# USBC_A.net
KiCad netlist of a schematic drawn in Altium Designer
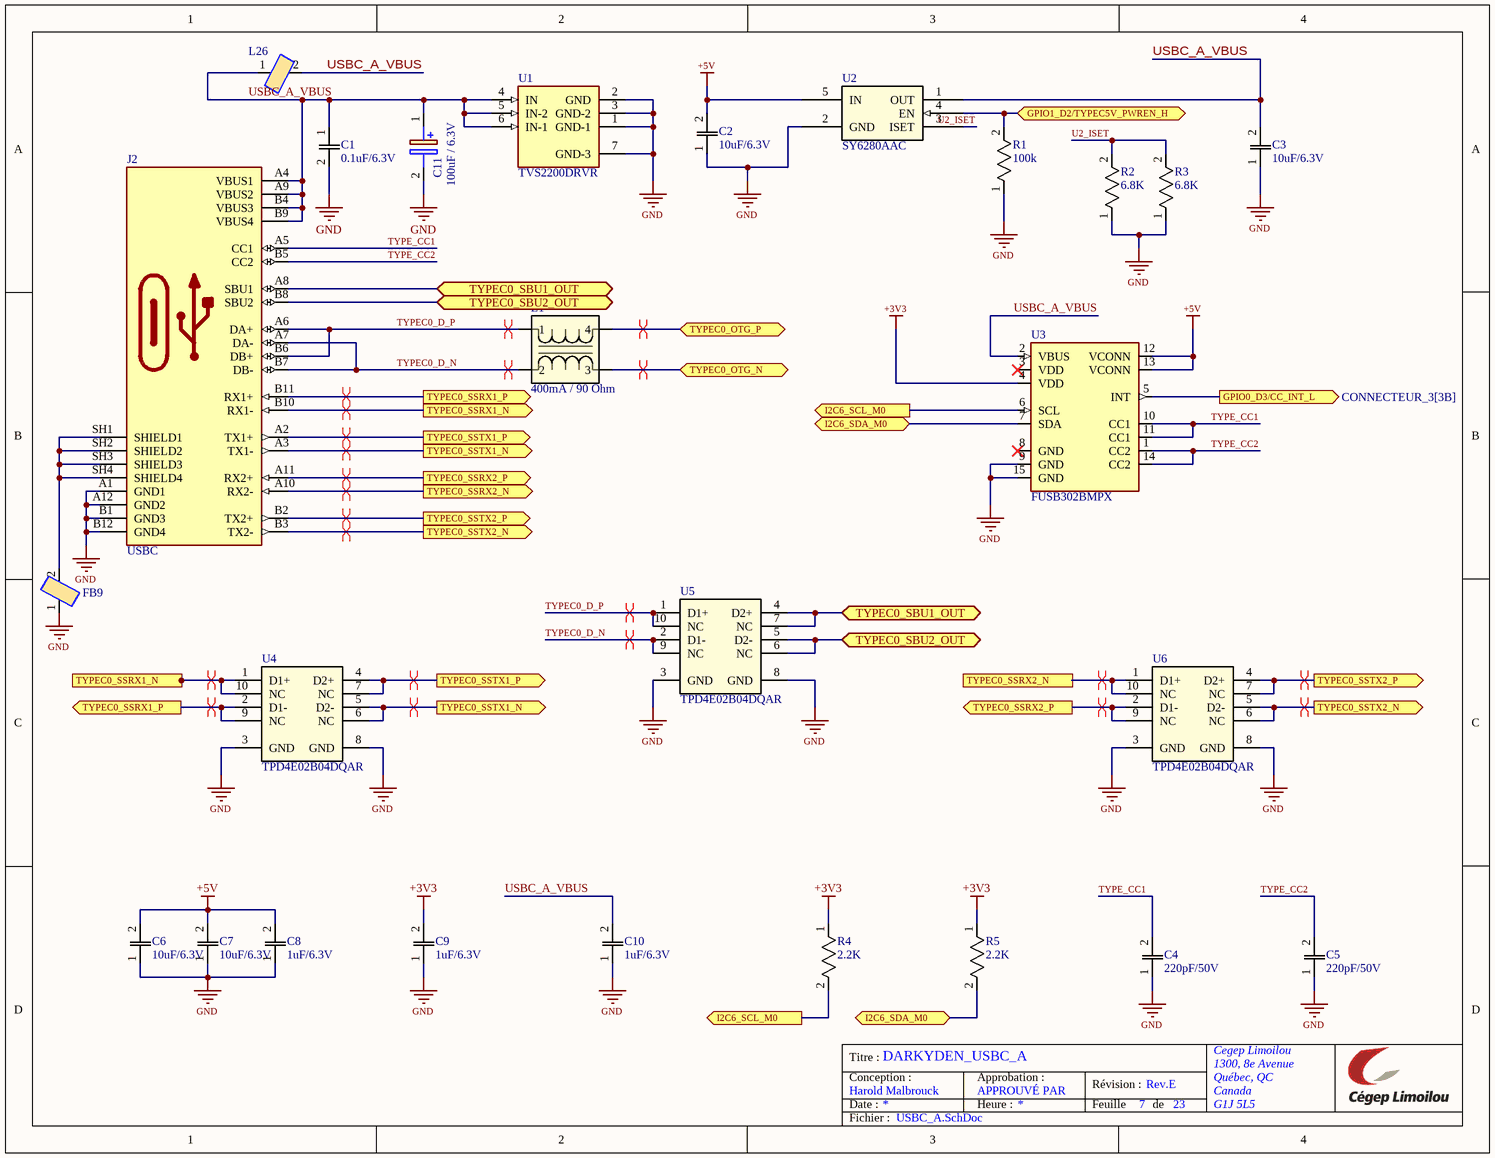
[diagram p0: USBC_A.SchDoc]

(export (version "E")
  (design (tool "Eeschema 10.0.6"))
  (components
    (comp (ref "C1")
      (value "0.1uF/6.3V")
      (footprint "C0805")
      (description "0.1uF 6.3V X7R 10% Pad SMD 0805 125C T/R")
      (fields
        (field (name "MANUFACTURER_PART_NUMBER") "C0805C104K9RACTU")
        (field (name "MOUSER PART NUMBER") "80-C0805C104K9R")
      )
      (libsource (lib "DARKYDEN") (part "C0805C104K9RACTU"))
    )
    (comp (ref "C2")
      (value "10uF/6.3V")
      (footprint "C0805")
      (fields
        (field (name "MANUFACTURER_PART_NUMBER") "C0805C106K9RACTU")
        (field (name "MOUSER PART NUMBER") "80-C0805C106K9R")
        (field (name "MANUFACTURER") "KEMET")
      )
      (libsource (lib "DARKYDEN") (part "C0805C106K9RACTU"))
    )
    (comp (ref "C3")
      (value "10uF/6.3V")
      (footprint "C0805")
      (fields
        (field (name "MANUFACTURER_PART_NUMBER") "C0805C106K9RACTU")
        (field (name "MOUSER PART NUMBER") "80-C0805C106K9R")
        (field (name "MANUFACTURER") "KEMET")
      )
      (libsource (lib "DARKYDEN") (part "C0805C106K9RACTU"))
    )
    (comp (ref "C4")
      (value "220pF/50V")
      (footprint "C0805")
      (description "Cap Ceramic 220pF 50V X7R 20% Pad SMD 0805 125C T/R")
      (fields
        (field (name "MANUFACTURER") "KEMET")
        (field (name "MANUFACTURER PART NUMBER") "C0805C221M5RACTU")
      )
      (libsource (lib "DARKYDEN") (part "C0805C221M5RACTU"))
    )
    (comp (ref "C5")
      (value "220pF/50V")
      (footprint "C0805")
      (description "Cap Ceramic 220pF 50V X7R 20% Pad SMD 0805 125C T/R")
      (fields
        (field (name "MANUFACTURER") "KEMET")
        (field (name "MANUFACTURER PART NUMBER") "C0805C221M5RACTU")
      )
      (libsource (lib "DARKYDEN") (part "C0805C221M5RACTU"))
    )
    (comp (ref "C6")
      (value "10uF/6.3V")
      (footprint "C0805")
      (fields
        (field (name "MANUFACTURER_PART_NUMBER") "C0805C106K9RACTU")
        (field (name "MOUSER PART NUMBER") "80-C0805C106K9R")
        (field (name "MANUFACTURER") "KEMET")
      )
      (libsource (lib "DARKYDEN") (part "C0805C106K9RACTU"))
    )
    (comp (ref "C7")
      (value "10uF/6.3V")
      (footprint "C0805")
      (fields
        (field (name "MANUFACTURER_PART_NUMBER") "C0805C106K9RACTU")
        (field (name "MOUSER PART NUMBER") "80-C0805C106K9R")
        (field (name "MANUFACTURER") "KEMET")
      )
      (libsource (lib "DARKYDEN") (part "C0805C106K9RACTU"))
    )
    (comp (ref "C8")
      (value "1uF/6.3V")
      (footprint "C0805")
      (description "1 uF, 6.3 V, ± 10%, X7R, 0805 [2012 Metric] Multilayer Ceramic Capacitor,")
      (fields
        (field (name "MANUFACTURER_PART_NUMBER") "C0805C105K9RACTU")
        (field (name "MOUSER PART NUMBER") "80-C0805C105K9R")
      )
      (libsource (lib "DARKYDEN") (part "C0805C105K9RACTU"))
    )
    (comp (ref "C9")
      (value "1uF/6.3V")
      (footprint "C0805")
      (description "1 uF, 6.3 V, ± 10%, X7R, 0805 [2012 Metric] Multilayer Ceramic Capacitor,")
      (fields
        (field (name "MANUFACTURER_PART_NUMBER") "C0805C105K9RACTU")
        (field (name "MOUSER PART NUMBER") "80-C0805C105K9R")
      )
      (libsource (lib "DARKYDEN") (part "C0805C105K9RACTU"))
    )
    (comp (ref "C10")
      (value "1uF/6.3V")
      (footprint "C0805")
      (description "1 uF, 6.3 V, ± 10%, X7R, 0805 [2012 Metric] Multilayer Ceramic Capacitor,")
      (fields
        (field (name "MANUFACTURER_PART_NUMBER") "C0805C105K9RACTU")
        (field (name "MOUSER PART NUMBER") "80-C0805C105K9R")
      )
      (libsource (lib "DARKYDEN") (part "C0805C105K9RACTU"))
    )
    (comp (ref "C11")
      (value "100uF / 6.3V")
      (footprint "SamacSys:EEE0GA101SR")
      (description "100uF 6.3V 20% Cap Aluminum Lytic  SMD 0.36 Ohm 240mA 2000h 105C Automotive T/R")
      (fields
        (field (name "MANUFACTURER_PART_NUMBER") "EEE-FPJ101UAR")
        (field (name "MOUSER PART NUMBER") "667-EEE-FPJ101UAR")
      )
      (libsource (lib "SamacSys") (part "EEE-FPJ101UAR"))
    )
    (comp (ref "FB9")
      (value "220R / 100MHz")
      (footprint "SamacSys:BLM18SP221SN1B")
      (description "Ferrite Beads Multi-Layer 220Ohm 25% 100MHz 2A 50mOhm DCR 0603 Paper T/R")
      (fields
        (field (name "MANUFACTURER_PART_NUMBER") "BLM18EG221SN1D")
        (field (name "MOUSER PART NUMBER") "81-BLM18EG221SN1D")
      )
      (libsource (lib "SamacSys") (part "BLM18EG221SN1D"))
    )
    (comp (ref "J2")
      (value "USBC")
      (footprint "USB_C")
      (fields (field (name "MF") "Molex") (field (name "MP") "2012670005"))
      (libsource (lib "DARKYDEN") (part "USBC"))
    )
    (comp (ref "L1")
      (value "400mA / 90 Ohm")
      (footprint "SamacSys:ACM20129002PT002")
      (description "Ferrite Beads Wirewound Common Mode Filter 90Ohm 100MHz 400mA 0805 T/R")
      (fields
        (field (name "MANUFACTURER_PART_NUMBER") "ACM2012-900-2P-T002")
        (field (name "MOUSER PART NUMBER") "810-ACM20129002PT002")
      )
      (libsource (lib "SamacSys") (part "ACM2012-900-2P-T002"))
    )
    (comp (ref "L26")
      (value "FBMJ2125HM210NT")
      (footprint "INDC2012X105N")
      (description "Ferrite Beads Power Chip 21Ohm 30% 100MHz 6A 0.004Ohm DCR 0805 Automotive T/R")
      (fields
        (field (name "MANUFACTURER") "Taiyo Yuden")
        (field (name "MOUSER PART NUMBER") "963-FBMJ2125HM210NT")
      )
      (libsource (lib "SamacSys") (part "FBMJ2125HM210NT"))
    )
    (comp (ref "R1")
      (value "100k")
      (footprint "SamacSys:RESC1608X55N")
      (description "100K Ohm 5%  Res Thick Film 0603 1/10W +/-200ppm/ßC Molded SMD Punched Carrier T/R")
      (fields
        (field (name "MANUFACTURER_PART_NUMBER") "ERJ-3GEYJ104V")
        (field (name "MOUSER PART NUMBER") "667-ERJ-3GEYJ104V")
      )
      (libsource (lib "DARKYDEN") (part "ERJ-3GEYJ104V"))
    )
    (comp (ref "R2")
      (value "6.8K")
      (footprint "SamacSys:RESC1608X55N")
      (description "6.8 kOhm, ± 5%, 100 mW, 0603 [1608 Metric], Thick Film, General Purpose")
      (fields
        (field (name "MANUFACTURER_PART_NUMBER") "ERJ-3GEYJ682V")
        (field (name "MANUFACTURER") "Panasonic")
      )
      (libsource (lib "DARKYDEN") (part "ERJ-3GEYJ682V"))
    )
    (comp (ref "R3")
      (value "6.8K")
      (footprint "SamacSys:RESC1608X55N")
      (description "6.8 kOhm, ± 5%, 100 mW, 0603 [1608 Metric], Thick Film, General Purpose")
      (fields
        (field (name "MANUFACTURER_PART_NUMBER") "ERJ-3GEYJ682V")
        (field (name "MANUFACTURER") "Panasonic")
      )
      (libsource (lib "DARKYDEN") (part "ERJ-3GEYJ682V"))
    )
    (comp (ref "R4")
      (value "2.2K")
      (footprint "SamacSys:RESC1608X55N")
      (description "2.2 kOhm, ï¿½ 5%, 100 mW, 0603 [1608 Metric], Thick Film, General Purpose")
      (fields
        (field (name "MANUFACTURER_PART_NUMBER") "ERJ-3GEYJ222V")
        (field (name "MOUSER PART NUMBER") "667-ERJ-3GEYJ222V")
      )
      (libsource (lib "DARKYDEN") (part "ERJ-3GEYJ222V"))
    )
    (comp (ref "R5")
      (value "2.2K")
      (footprint "SamacSys:RESC1608X55N")
      (description "2.2 kOhm, ï¿½ 5%, 100 mW, 0603 [1608 Metric], Thick Film, General Purpose")
      (fields
        (field (name "MANUFACTURER_PART_NUMBER") "ERJ-3GEYJ222V")
        (field (name "MOUSER PART NUMBER") "667-ERJ-3GEYJ222V")
      )
      (libsource (lib "DARKYDEN") (part "ERJ-3GEYJ222V"))
    )
    (comp (ref "U1")
      (value "TVS2200DRVR")
      (footprint "SON65P200X200X80-7N")
      (description "ESD Suppressors / TVS Diodes 22V flat-clamp surge protection device 6-WSON -40 to 125")
      (fields (field (name "MF") "Texas Instruments"))
      (libsource (lib "TVS2200") (part "TVS2200DRVR"))
    )
    (comp (ref "U2")
      (value "SY6280AAC")
      (footprint "SamacSys:SOT95P285X140-5N")
      (description "2.4V~5.5V 80mΩ Active High 1 High-side switch SOT-23-5 Power Distribution Switches ROHS")
      (libsource (lib "SamacSys") (part "SY6280AAC"))
    )
    (comp (ref "U3")
      (value "FUSB302BMPX")
      (footprint "SamacSys:QFN50P250X250X80-15N")
      (description "USB Controller USB 3.1 USB Interface 14-MLP (2.5x2.5)")
      (fields (field (name "MOUSER PART NUMBER") "512-FUSB302BMPX"))
      (libsource (lib "SamacSys") (part "FUSB302BMPX"))
    )
    (comp (ref "U4")
      (value "TPD4E02B04DQAR")
      (footprint "DQA0010A")
      (description "TVS DIODE 3.6V 8.8V 10USON / 4-Channel ESD Protection Diode for USB Type-C and HDMI 2.0")
      (fields (field (name "MANUFACTURER") "Texas Instruments"))
      (libsource (lib "TPD4E02B04DQAR") (part "TPD4E02B04DQAR"))
    )
    (comp (ref "U5")
      (value "TPD4E02B04DQAR")
      (footprint "DQA0010A")
      (description "TVS DIODE 3.6V 8.8V 10USON / 4-Channel ESD Protection Diode for USB Type-C and HDMI 2.0")
      (fields (field (name "MANUFACTURER") "Texas Instruments"))
      (libsource (lib "TPD4E02B04DQAR") (part "TPD4E02B04DQAR"))
    )
    (comp (ref "U6")
      (value "TPD4E02B04DQAR")
      (footprint "DQA0010A")
      (description "TVS DIODE 3.6V 8.8V 10USON / 4-Channel ESD Protection Diode for USB Type-C and HDMI 2.0")
      (fields (field (name "MANUFACTURER") "Texas Instruments"))
      (libsource (lib "TPD4E02B04DQAR") (part "TPD4E02B04DQAR"))
    )
  )
  (nets
    (net (code "1") (name "+3V3") (class "Default")
      (node (ref "C9") (pin "2") (pinfunction "2_2") (pintype "passive"))
      (node (ref "R4") (pin "1") (pinfunction "1_1") (pintype "passive"))
      (node (ref "R5") (pin "1") (pinfunction "1_1") (pintype "passive"))
      (node (ref "U3") (pin "4") (pinfunction "VDD_4") (pintype "power_in"))
    )
    (net (code "2") (name "+5V") (class "Default")
      (node (ref "C2") (pin "2") (pinfunction "2_2") (pintype "passive"))
      (node (ref "C6") (pin "2") (pinfunction "2_2") (pintype "passive"))
      (node (ref "C7") (pin "2") (pinfunction "2_2") (pintype "passive"))
      (node (ref "C8") (pin "2") (pinfunction "2_2") (pintype "passive"))
      (node (ref "U2") (pin "5") (pinfunction "IN_5") (pintype "power_in"))
      (node (ref "U3") (pin "12") (pinfunction "VCONN_12") (pintype "power_in"))
      (node (ref "U3") (pin "13") (pinfunction "VCONN_13") (pintype "power_in"))
    )
    (net (code "3") (name "/GPIO0_D3{slash}CC_INT_L") (class "Default")
      (node (ref "U3") (pin "5") (pinfunction "INT_5") (pintype "output"))
    )
    (net (code "4") (name "/GPIO1_D2{slash}TYPEC5V_PWREN_H") (class "Default")
      (node (ref "R1") (pin "2") (pinfunction "2_2") (pintype "passive"))
      (node (ref "U2") (pin "4") (pinfunction "EN_4") (pintype "input"))
    )
    (net (code "5") (name "/I2C6_SCL_M0") (class "Default")
      (node (ref "R4") (pin "2") (pinfunction "2_2") (pintype "passive"))
      (node (ref "U3") (pin "6") (pinfunction "SCL_6") (pintype "input"))
    )
    (net (code "6") (name "/I2C6_SDA_M0") (class "Default")
      (node (ref "R5") (pin "2") (pinfunction "2_2") (pintype "passive"))
      (node (ref "U3") (pin "7") (pinfunction "SDA_7") (pintype "bidirectional"))
    )
    (net (code "7") (name "/TYPEC0_D_N") (class "Default")
      (node (ref "J2") (pin "A7") (pinfunction "DA-_A7") (pintype "bidirectional"))
      (node (ref "J2") (pin "B7") (pinfunction "DB-_B7") (pintype "bidirectional"))
      (node (ref "L1") (pin "2") (pinfunction "2_2") (pintype "passive"))
      (node (ref "U5") (pin "2") (pinfunction "D1-_2") (pintype "passive"))
      (node (ref "U5") (pin "9") (pinfunction "NC_9") (pintype "passive"))
    )
    (net (code "8") (name "/TYPEC0_D_P") (class "Default")
      (node (ref "J2") (pin "A6") (pinfunction "DA+_A6") (pintype "bidirectional"))
      (node (ref "J2") (pin "B6") (pinfunction "DB+_B6") (pintype "bidirectional"))
      (node (ref "L1") (pin "1") (pinfunction "1_1") (pintype "passive"))
      (node (ref "U5") (pin "1") (pinfunction "D1+_1") (pintype "passive"))
      (node (ref "U5") (pin "10") (pinfunction "NC_10") (pintype "passive"))
    )
    (net (code "9") (name "/TYPEC0_OTG_N") (class "Default")
      (node (ref "L1") (pin "3") (pinfunction "3_3") (pintype "passive"))
    )
    (net (code "10") (name "/TYPEC0_OTG_P") (class "Default")
      (node (ref "L1") (pin "4") (pinfunction "4_4") (pintype "passive"))
    )
    (net (code "11") (name "/TYPEC0_SBU1_OUT") (class "Default")
      (node (ref "J2") (pin "A8") (pinfunction "SBU1_A8") (pintype "bidirectional"))
      (node (ref "U5") (pin "4") (pinfunction "D2+_4") (pintype "passive"))
      (node (ref "U5") (pin "7") (pinfunction "NC_7") (pintype "passive"))
    )
    (net (code "12") (name "/TYPEC0_SBU2_OUT") (class "Default")
      (node (ref "J2") (pin "B8") (pinfunction "SBU2_B8") (pintype "bidirectional"))
      (node (ref "U5") (pin "5") (pinfunction "D2-_5") (pintype "passive"))
      (node (ref "U5") (pin "6") (pinfunction "NC_6") (pintype "passive"))
    )
    (net (code "13") (name "/TYPEC0_SSRX1_N") (class "Default")
      (node (ref "J2") (pin "B10") (pinfunction "RX1-_B10") (pintype "input"))
      (node (ref "U4") (pin "1") (pinfunction "D1+_1") (pintype "passive"))
      (node (ref "U4") (pin "10") (pinfunction "NC_10") (pintype "passive"))
    )
    (net (code "14") (name "/TYPEC0_SSRX1_P") (class "Default")
      (node (ref "J2") (pin "B11") (pinfunction "RX1+_B11") (pintype "input"))
      (node (ref "U4") (pin "2") (pinfunction "D1-_2") (pintype "passive"))
      (node (ref "U4") (pin "9") (pinfunction "NC_9") (pintype "passive"))
    )
    (net (code "15") (name "/TYPEC0_SSRX2_N") (class "Default")
      (node (ref "J2") (pin "A10") (pinfunction "RX2-_A10") (pintype "input"))
      (node (ref "U6") (pin "1") (pinfunction "D1+_1") (pintype "passive"))
      (node (ref "U6") (pin "10") (pinfunction "NC_10") (pintype "passive"))
    )
    (net (code "16") (name "/TYPEC0_SSRX2_P") (class "Default")
      (node (ref "J2") (pin "A11") (pinfunction "RX2+_A11") (pintype "input"))
      (node (ref "U6") (pin "2") (pinfunction "D1-_2") (pintype "passive"))
      (node (ref "U6") (pin "9") (pinfunction "NC_9") (pintype "passive"))
    )
    (net (code "17") (name "/TYPEC0_SSTX1_N") (class "Default")
      (node (ref "J2") (pin "A3") (pinfunction "TX1-_A3") (pintype "output"))
      (node (ref "U4") (pin "5") (pinfunction "D2-_5") (pintype "passive"))
      (node (ref "U4") (pin "6") (pinfunction "NC_6") (pintype "passive"))
    )
    (net (code "18") (name "/TYPEC0_SSTX1_P") (class "Default")
      (node (ref "J2") (pin "A2") (pinfunction "TX1+_A2") (pintype "output"))
      (node (ref "U4") (pin "4") (pinfunction "D2+_4") (pintype "passive"))
      (node (ref "U4") (pin "7") (pinfunction "NC_7") (pintype "passive"))
    )
    (net (code "19") (name "/TYPEC0_SSTX2_N") (class "Default")
      (node (ref "J2") (pin "B3") (pinfunction "TX2-_B3") (pintype "output"))
      (node (ref "U6") (pin "5") (pinfunction "D2-_5") (pintype "passive"))
      (node (ref "U6") (pin "6") (pinfunction "NC_6") (pintype "passive"))
    )
    (net (code "20") (name "/TYPEC0_SSTX2_P") (class "Default")
      (node (ref "J2") (pin "B2") (pinfunction "TX2+_B2") (pintype "output"))
      (node (ref "U6") (pin "4") (pinfunction "D2+_4") (pintype "passive"))
      (node (ref "U6") (pin "7") (pinfunction "NC_7") (pintype "passive"))
    )
    (net (code "21") (name "/TYPE_CC1") (class "Default")
      (node (ref "C4") (pin "2") (pinfunction "2_2") (pintype "passive"))
      (node (ref "J2") (pin "A5") (pinfunction "CC1_A5") (pintype "bidirectional"))
      (node (ref "U3") (pin "10") (pinfunction "CC1_10") (pintype "bidirectional"))
      (node (ref "U3") (pin "11") (pinfunction "CC1_11") (pintype "bidirectional"))
    )
    (net (code "22") (name "/TYPE_CC2") (class "Default")
      (node (ref "C5") (pin "2") (pinfunction "2_2") (pintype "passive"))
      (node (ref "J2") (pin "B5") (pinfunction "CC2_B5") (pintype "bidirectional"))
      (node (ref "U3") (pin "1") (pinfunction "CC2_1") (pintype "bidirectional"))
      (node (ref "U3") (pin "14") (pinfunction "CC2_14") (pintype "bidirectional"))
    )
    (net (code "23") (name "/U2_ISET") (class "Default")
      (node (ref "R2") (pin "2") (pinfunction "2_2") (pintype "passive"))
      (node (ref "R3") (pin "2") (pinfunction "2_2") (pintype "passive"))
      (node (ref "U2") (pin "3") (pinfunction "ISET_3") (pintype "passive"))
    )
    (net (code "24") (name "/USBC_A_VBUS") (class "Default")
      (node (ref "C1") (pin "1") (pinfunction "1_1") (pintype "passive"))
      (node (ref "C10") (pin "2") (pinfunction "2_2") (pintype "passive"))
      (node (ref "C11") (pin "1") (pinfunction "+_1") (pintype "passive"))
      (node (ref "C3") (pin "2") (pinfunction "2_2") (pintype "passive"))
      (node (ref "J2") (pin "A4") (pinfunction "VBUS1_A4") (pintype "power_in"))
      (node (ref "J2") (pin "A9") (pinfunction "VBUS2_A9") (pintype "power_in"))
      (node (ref "J2") (pin "B4") (pinfunction "VBUS3_B4") (pintype "power_in"))
      (node (ref "J2") (pin "B9") (pinfunction "VBUS4_B9") (pintype "power_in"))
      (node (ref "L26") (pin "1") (pinfunction "1_1") (pintype "passive"))
      (node (ref "L26") (pin "2") (pinfunction "2_2") (pintype "passive"))
      (node (ref "U1") (pin "4") (pinfunction "IN_4") (pintype "input"))
      (node (ref "U1") (pin "5") (pinfunction "IN-2_5") (pintype "input"))
      (node (ref "U1") (pin "6") (pinfunction "IN-1_6") (pintype "input"))
      (node (ref "U2") (pin "1") (pinfunction "OUT_1") (pintype "power_in"))
      (node (ref "U3") (pin "2") (pinfunction "VBUS_2") (pintype "input"))
    )
    (net (code "25") (name "GND") (class "Default")
      (node (ref "C1") (pin "2") (pinfunction "2_2") (pintype "passive"))
      (node (ref "C10") (pin "1") (pinfunction "1_1") (pintype "passive"))
      (node (ref "C11") (pin "2") (pinfunction "-_2") (pintype "passive"))
      (node (ref "C2") (pin "1") (pinfunction "1_1") (pintype "passive"))
      (node (ref "C3") (pin "1") (pinfunction "1_1") (pintype "passive"))
      (node (ref "C4") (pin "1") (pinfunction "1_1") (pintype "passive"))
      (node (ref "C5") (pin "1") (pinfunction "1_1") (pintype "passive"))
      (node (ref "C6") (pin "1") (pinfunction "1_1") (pintype "passive"))
      (node (ref "C7") (pin "1") (pinfunction "1_1") (pintype "passive"))
      (node (ref "C8") (pin "1") (pinfunction "1_1") (pintype "passive"))
      (node (ref "C9") (pin "1") (pinfunction "1_1") (pintype "passive"))
      (node (ref "FB9") (pin "1") (pinfunction "1_1") (pintype "passive"))
      (node (ref "J2") (pin "A1") (pinfunction "GND1_A1") (pintype "passive"))
      (node (ref "J2") (pin "A12") (pinfunction "GND2_A12") (pintype "passive"))
      (node (ref "J2") (pin "B1") (pinfunction "GND3_B1") (pintype "passive"))
      (node (ref "J2") (pin "B12") (pinfunction "GND4_B12") (pintype "passive"))
      (node (ref "R1") (pin "1") (pinfunction "1_1") (pintype "passive"))
      (node (ref "R2") (pin "1") (pinfunction "1_1") (pintype "passive"))
      (node (ref "R3") (pin "1") (pinfunction "1_1") (pintype "passive"))
      (node (ref "U1") (pin "1") (pinfunction "GND-1_1") (pintype "passive"))
      (node (ref "U1") (pin "2") (pinfunction "GND_2") (pintype "passive"))
      (node (ref "U1") (pin "3") (pinfunction "GND-2_3") (pintype "passive"))
      (node (ref "U1") (pin "7") (pinfunction "GND-3_7") (pintype "passive"))
      (node (ref "U2") (pin "2") (pinfunction "GND_2") (pintype "passive"))
      (node (ref "U3") (pin "15") (pinfunction "GND_15") (pintype "passive"))
      (node (ref "U3") (pin "9") (pinfunction "GND_9") (pintype "passive"))
      (node (ref "U4") (pin "3") (pinfunction "GND_3") (pintype "passive"))
      (node (ref "U4") (pin "8") (pinfunction "GND_8") (pintype "passive"))
      (node (ref "U5") (pin "3") (pinfunction "GND_3") (pintype "passive"))
      (node (ref "U5") (pin "8") (pinfunction "GND_8") (pintype "passive"))
      (node (ref "U6") (pin "3") (pinfunction "GND_3") (pintype "passive"))
      (node (ref "U6") (pin "8") (pinfunction "GND_8") (pintype "passive"))
    )
    (net (code "26") (name "Net-(J2-SHIELD1)") (class "Default")
      (node (ref "FB9") (pin "2") (pinfunction "2_2") (pintype "passive"))
      (node (ref "J2") (pin "SH1") (pinfunction "SHIELD1_SH1") (pintype "passive"))
      (node (ref "J2") (pin "SH2") (pinfunction "SHIELD2_SH2") (pintype "passive"))
      (node (ref "J2") (pin "SH3") (pinfunction "SHIELD3_SH3") (pintype "passive"))
      (node (ref "J2") (pin "SH4") (pinfunction "SHIELD4_SH4") (pintype "passive"))
    )
    (net (code "27") (name "unconnected-(U3-GND-Pad8)") (class "Default")
      (node (ref "U3") (pin "8") (pinfunction "GND_8") (pintype "passive+no_connect"))
    )
    (net (code "28") (name "unconnected-(U3-VDD-Pad3)") (class "Default")
      (node (ref "U3") (pin "3") (pinfunction "VDD_3") (pintype "power_in+no_connect"))
    )
  )
)
